# PWR.net
KiCad netlist of a schematic drawn in Altium Designer
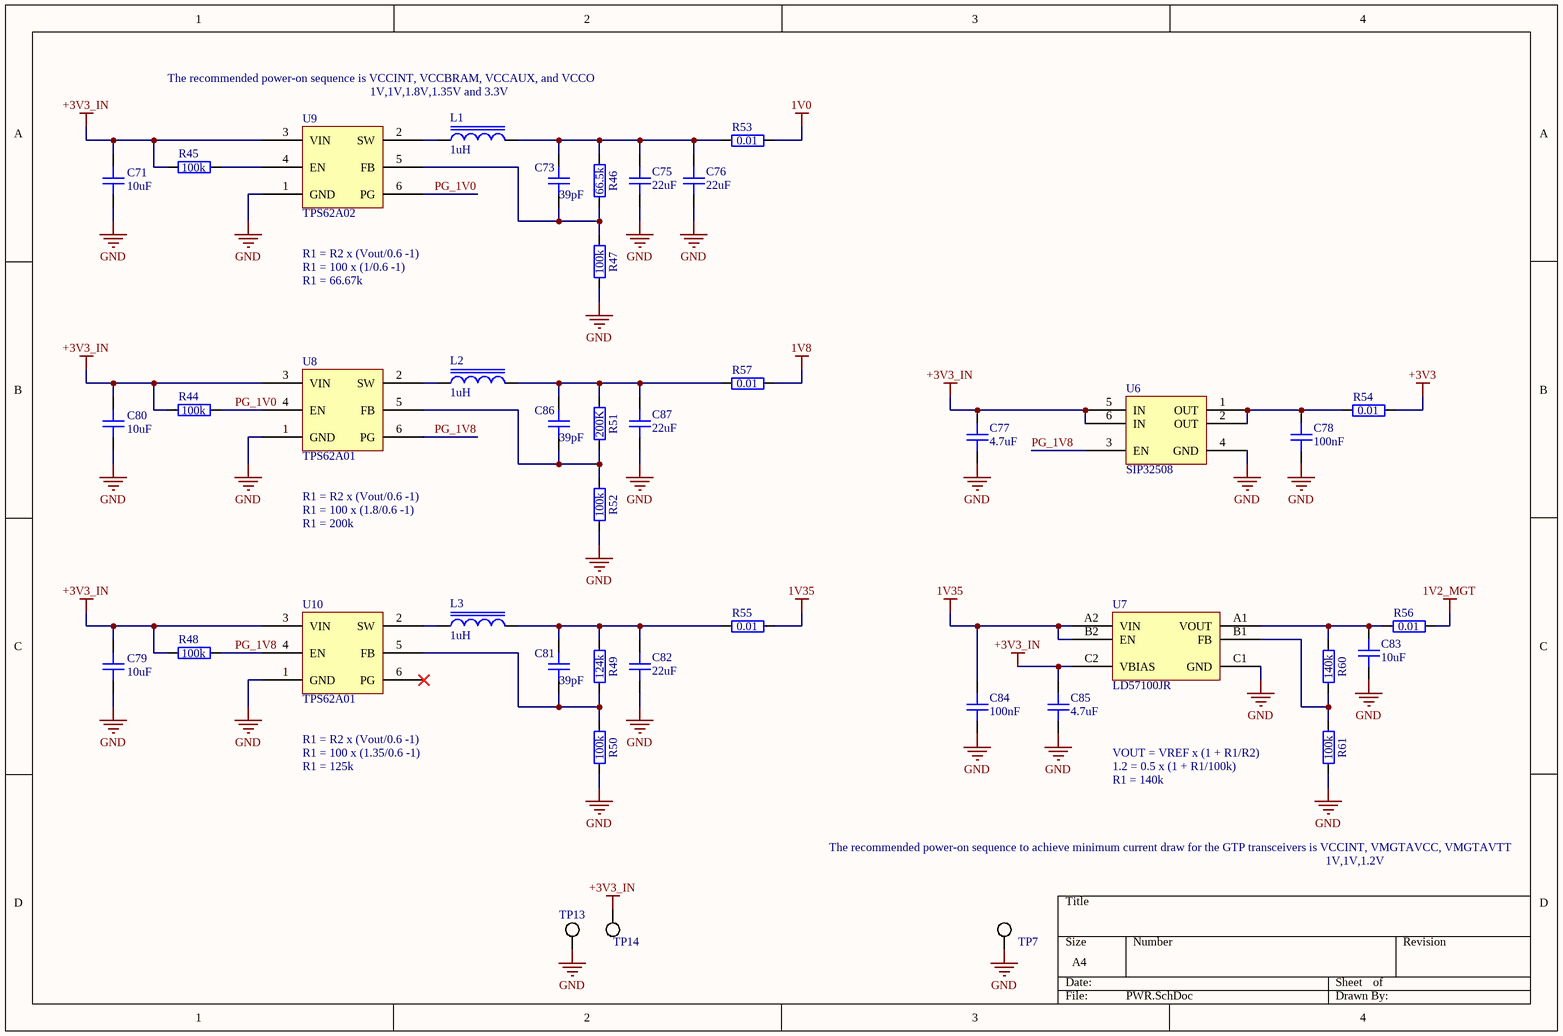
[diagram p0: PWR.SchDoc]

(export (version "E")
  (design (tool "Eeschema 10.0.6"))
  (components
    (comp (ref "C71")
      (value "10uF")
      (footprint "GEN_C_0603")
      (libsource (lib "DSO") (part "CAP 10uF 10V X5R 0603"))
    )
    (comp (ref "C73")
      (value "39pF")
      (footprint "GEN_C_0402")
      (libsource (lib "DSO") (part "CAP 39pF 50V C0G 0402"))
    )
    (comp (ref "C75")
      (value "22uF")
      (footprint "GEN_C_0805")
      (libsource (lib "DSO") (part "CAP 22uF 25V X5R 0805"))
    )
    (comp (ref "C76")
      (value "22uF")
      (footprint "GEN_C_0805")
      (libsource (lib "DSO") (part "CAP 22uF 25V X5R 0805"))
    )
    (comp (ref "C77")
      (value "4.7uF")
      (footprint "GEN_C_0402")
      (libsource (lib "DSO") (part "CAP 4.7uF 6.3V X5R 0402"))
    )
    (comp (ref "C78")
      (value "100nF")
      (footprint "GEN_C_0402")
      (libsource (lib "DSO") (part "CAP 100nF 16V X7R 0402"))
    )
    (comp (ref "C79")
      (value "10uF")
      (footprint "GEN_C_0603")
      (libsource (lib "DSO") (part "CAP 10uF 10V X5R 0603"))
    )
    (comp (ref "C80")
      (value "10uF")
      (footprint "GEN_C_0603")
      (libsource (lib "DSO") (part "CAP 10uF 10V X5R 0603"))
    )
    (comp (ref "C81")
      (value "39pF")
      (footprint "GEN_C_0402")
      (libsource (lib "DSO") (part "CAP 39pF 50V C0G 0402"))
    )
    (comp (ref "C82")
      (value "22uF")
      (footprint "GEN_C_0805")
      (libsource (lib "DSO") (part "CAP 22uF 25V X5R 0805"))
    )
    (comp (ref "C83")
      (value "10uF")
      (footprint "GEN_C_0603")
      (libsource (lib "DSO") (part "CAP 10uF 10V X5R 0603"))
    )
    (comp (ref "C84")
      (value "100nF")
      (footprint "GEN_C_0402")
      (libsource (lib "DSO") (part "CAP 100nF 16V X7R 0402"))
    )
    (comp (ref "C85")
      (value "4.7uF")
      (footprint "GEN_C_0402")
      (libsource (lib "DSO") (part "CAP 4.7uF 6.3V X5R 0402"))
    )
    (comp (ref "C86")
      (value "39pF")
      (footprint "GEN_C_0402")
      (libsource (lib "DSO") (part "CAP 39pF 50V C0G 0402"))
    )
    (comp (ref "C87")
      (value "22uF")
      (footprint "GEN_C_0805")
      (libsource (lib "DSO") (part "CAP 22uF 25V X5R 0805"))
    )
    (comp (ref "L1")
      (value "1uH")
      (footprint "GEN_L_1210")
      (libsource (lib "DSO") (part "IND 1uH 5.5A 32 MOHM 1210"))
    )
    (comp (ref "L2")
      (value "1uH")
      (footprint "GEN_L_1210")
      (libsource (lib "DSO") (part "IND 1uH 5.5A 32 MOHM 1210"))
    )
    (comp (ref "L3")
      (value "1uH")
      (footprint "GEN_L_1210")
      (libsource (lib "DSO") (part "IND 1uH 5.5A 32 MOHM 1210"))
    )
    (comp (ref "R44")
      (value "100k")
      (footprint "GEN_R_0402")
      (fields (field (name "TOLERANCE") "1%"))
      (libsource (lib "") (part "RES 100K OHM 1% 1/10W 0402_1"))
    )
    (comp (ref "R45")
      (value "100k")
      (footprint "GEN_R_0402")
      (fields (field (name "TOLERANCE") "1%"))
      (libsource (lib "") (part "RES 100K OHM 1% 1/10W 0402_1"))
    )
    (comp (ref "R46")
      (value "66.5k")
      (footprint "GEN_R_0402")
      (fields (field (name "TOLERANCE") "1%"))
      (libsource (lib "DSO") (part "RES 66.5K OHM 1% 1/16W 0402"))
    )
    (comp (ref "R47")
      (value "100k")
      (footprint "GEN_R_0402")
      (fields (field (name "TOLERANCE") "1%"))
      (libsource (lib "DSO") (part "RES 100K OHM 1% 1/10W 0402"))
    )
    (comp (ref "R48")
      (value "100k")
      (footprint "GEN_R_0402")
      (fields (field (name "TOLERANCE") "1%"))
      (libsource (lib "") (part "RES 100K OHM 1% 1/10W 0402_1"))
    )
    (comp (ref "R49")
      (value "124k")
      (footprint "GEN_R_0402")
      (fields (field (name "TOLERANCE") "1%"))
      (libsource (lib "DSO") (part "RES 124K OHM 1% 1/10W 0402"))
    )
    (comp (ref "R50")
      (value "100k")
      (footprint "GEN_R_0402")
      (fields (field (name "TOLERANCE") "1%"))
      (libsource (lib "DSO") (part "RES 100K OHM 1% 1/10W 0402"))
    )
    (comp (ref "R51")
      (value "200K")
      (footprint "GEN_R_0402")
      (fields (field (name "TOLERANCE") "1%"))
      (libsource (lib "DSO") (part "RES 200K OHM 1% 1/16W 0402"))
    )
    (comp (ref "R52")
      (value "100k")
      (footprint "GEN_R_0402")
      (fields (field (name "TOLERANCE") "1%"))
      (libsource (lib "DSO") (part "RES 100K OHM 1% 1/10W 0402"))
    )
    (comp (ref "R53")
      (value "0.01")
      (footprint "GEN_R_0603")
      (fields (field (name "TOLERANCE") "1%"))
      (libsource (lib "DSO") (part "RES 0.01 OHM 1% 1/4W 0603"))
    )
    (comp (ref "R54")
      (value "0.01")
      (footprint "GEN_R_0603")
      (fields (field (name "TOLERANCE") "1%"))
      (libsource (lib "DSO") (part "RES 0.01 OHM 1% 1/4W 0603"))
    )
    (comp (ref "R55")
      (value "0.01")
      (footprint "GEN_R_0603")
      (fields (field (name "TOLERANCE") "1%"))
      (libsource (lib "DSO") (part "RES 0.01 OHM 1% 1/4W 0603"))
    )
    (comp (ref "R56")
      (value "0.01")
      (footprint "GEN_R_0603")
      (fields (field (name "TOLERANCE") "1%"))
      (libsource (lib "DSO") (part "RES 0.01 OHM 1% 1/4W 0603"))
    )
    (comp (ref "R57")
      (value "0.01")
      (footprint "GEN_R_0603")
      (fields (field (name "TOLERANCE") "1%"))
      (libsource (lib "DSO") (part "RES 0.01 OHM 1% 1/4W 0603"))
    )
    (comp (ref "R60")
      (value "140k")
      (footprint "GEN_R_0402")
      (fields (field (name "TOLERANCE") "1%"))
      (libsource (lib "DSO") (part "RES 140K OHM 1% 1/10W 0402"))
    )
    (comp (ref "R61")
      (value "100k")
      (footprint "GEN_R_0402")
      (fields (field (name "TOLERANCE") "1%"))
      (libsource (lib "DSO") (part "RES 100K OHM 1% 1/10W 0402"))
    )
    (comp (ref "TP7") (value "PCB") (footprint "GEN_TP_PCB") (libsource (lib "DSO") (part "TP PCB 1mm")))
    (comp (ref "TP13") (value "PCB") (footprint "GEN_TP_PCB") (libsource (lib "DSO") (part "TP PCB 1mm")))
    (comp (ref "TP14") (value "PCB") (footprint "GEN_TP_PCB") (libsource (lib "DSO") (part "TP PCB 1mm")))
    (comp (ref "U6")
      (value "SIP32508")
      (footprint "VISH_TSOT6")
      (libsource (lib "DSO") (part "IC SWITCH LOAD SIP32508"))
    )
    (comp (ref "U7")
      (value "LD57100JR")
      (footprint "ST_FlipChip6")
      (libsource (lib "DSO") (part "IC LDO LD57100JR"))
    )
    (comp (ref "U8")
      (value "TPS62A01")
      (footprint "TI_SOT563_DRL0006A")
      (libsource (lib "DSO") (part "IC BUCK TPS62A01"))
    )
    (comp (ref "U9")
      (value "TPS62A02")
      (footprint "TI_SOT563_DRL0006A")
      (libsource (lib "DSO") (part "IC BUCK TPS62A02"))
    )
    (comp (ref "U10")
      (value "TPS62A01")
      (footprint "TI_SOT563_DRL0006A")
      (libsource (lib "DSO") (part "IC BUCK TPS62A01"))
    )
  )
  (nets
    (net (code "1") (name "+3V3") (class "Default")
      (node (ref "R54") (pin "2") (pinfunction "2_2") (pintype "passive"))
    )
    (net (code "2") (name "+3V3_IN") (class "Default")
      (node (ref "C71") (pin "2") (pinfunction "2_2") (pintype "passive"))
      (node (ref "C77") (pin "2") (pinfunction "2_2") (pintype "passive"))
      (node (ref "C79") (pin "2") (pinfunction "2_2") (pintype "passive"))
      (node (ref "C80") (pin "2") (pinfunction "2_2") (pintype "passive"))
      (node (ref "C85") (pin "2") (pinfunction "2_2") (pintype "passive"))
      (node (ref "R44") (pin "2") (pinfunction "2_2") (pintype "passive"))
      (node (ref "R45") (pin "2") (pinfunction "2_2") (pintype "passive"))
      (node (ref "R48") (pin "2") (pinfunction "2_2") (pintype "passive"))
      (node (ref "TP14") (pin "1") (pinfunction "1_1") (pintype "passive"))
      (node (ref "U10") (pin "3") (pinfunction "VIN_3") (pintype "power_in"))
      (node (ref "U6") (pin "5") (pinfunction "IN_5") (pintype "passive"))
      (node (ref "U6") (pin "6") (pinfunction "IN_6") (pintype "passive"))
      (node (ref "U7") (pin "C2") (pinfunction "VBIAS_C2") (pintype "passive"))
      (node (ref "U8") (pin "3") (pinfunction "VIN_3") (pintype "power_in"))
      (node (ref "U9") (pin "3") (pinfunction "VIN_3") (pintype "power_in"))
    )
    (net (code "3") (name "/PG_1V0") (class "Default")
      (node (ref "R44") (pin "1") (pinfunction "1_1") (pintype "passive"))
      (node (ref "U8") (pin "4") (pinfunction "EN_4") (pintype "passive"))
      (node (ref "U9") (pin "6") (pinfunction "PG_6") (pintype "passive"))
    )
    (net (code "4") (name "/PG_1V8") (class "Default")
      (node (ref "R48") (pin "1") (pinfunction "1_1") (pintype "passive"))
      (node (ref "U10") (pin "4") (pinfunction "EN_4") (pintype "passive"))
      (node (ref "U6") (pin "3") (pinfunction "EN_3") (pintype "passive"))
      (node (ref "U8") (pin "6") (pinfunction "PG_6") (pintype "passive"))
    )
    (net (code "5") (name "1V0") (class "Default")
      (node (ref "R53") (pin "2") (pinfunction "2_2") (pintype "passive"))
    )
    (net (code "6") (name "1V2_MGT") (class "Default")
      (node (ref "R56") (pin "2") (pinfunction "2_2") (pintype "passive"))
    )
    (net (code "7") (name "1V8") (class "Default")
      (node (ref "R57") (pin "2") (pinfunction "2_2") (pintype "passive"))
    )
    (net (code "8") (name "1V35") (class "Default")
      (node (ref "C84") (pin "2") (pinfunction "2_2") (pintype "passive"))
      (node (ref "R55") (pin "2") (pinfunction "2_2") (pintype "passive"))
      (node (ref "U7") (pin "A2") (pinfunction "VIN_A2") (pintype "passive"))
      (node (ref "U7") (pin "B2") (pinfunction "EN_B2") (pintype "passive"))
    )
    (net (code "9") (name "GND") (class "Default")
      (node (ref "C71") (pin "1") (pinfunction "1_1") (pintype "passive"))
      (node (ref "C75") (pin "1") (pinfunction "1_1") (pintype "passive"))
      (node (ref "C76") (pin "1") (pinfunction "1_1") (pintype "passive"))
      (node (ref "C77") (pin "1") (pinfunction "1_1") (pintype "passive"))
      (node (ref "C78") (pin "1") (pinfunction "1_1") (pintype "passive"))
      (node (ref "C79") (pin "1") (pinfunction "1_1") (pintype "passive"))
      (node (ref "C80") (pin "1") (pinfunction "1_1") (pintype "passive"))
      (node (ref "C82") (pin "1") (pinfunction "1_1") (pintype "passive"))
      (node (ref "C83") (pin "1") (pinfunction "1_1") (pintype "passive"))
      (node (ref "C84") (pin "1") (pinfunction "1_1") (pintype "passive"))
      (node (ref "C85") (pin "1") (pinfunction "1_1") (pintype "passive"))
      (node (ref "C87") (pin "1") (pinfunction "1_1") (pintype "passive"))
      (node (ref "R47") (pin "1") (pinfunction "1_1") (pintype "passive"))
      (node (ref "R50") (pin "1") (pinfunction "1_1") (pintype "passive"))
      (node (ref "R52") (pin "1") (pinfunction "1_1") (pintype "passive"))
      (node (ref "R61") (pin "1") (pinfunction "1_1") (pintype "passive"))
      (node (ref "TP13") (pin "1") (pinfunction "1_1") (pintype "passive"))
      (node (ref "TP7") (pin "1") (pinfunction "1_1") (pintype "passive"))
      (node (ref "U10") (pin "1") (pinfunction "GND_1") (pintype "power_in"))
      (node (ref "U6") (pin "4") (pinfunction "GND_4") (pintype "passive"))
      (node (ref "U7") (pin "C1") (pinfunction "GND_C1") (pintype "passive"))
      (node (ref "U8") (pin "1") (pinfunction "GND_1") (pintype "power_in"))
      (node (ref "U9") (pin "1") (pinfunction "GND_1") (pintype "power_in"))
    )
    (net (code "10") (name "Net-(C73-Pad2)") (class "Default")
      (node (ref "C73") (pin "2") (pinfunction "2_2") (pintype "passive"))
      (node (ref "C75") (pin "2") (pinfunction "2_2") (pintype "passive"))
      (node (ref "C76") (pin "2") (pinfunction "2_2") (pintype "passive"))
      (node (ref "L1") (pin "2") (pinfunction "2_2") (pintype "passive"))
      (node (ref "R46") (pin "2") (pinfunction "2_2") (pintype "passive"))
      (node (ref "R53") (pin "1") (pinfunction "1_1") (pintype "passive"))
    )
    (net (code "11") (name "Net-(C78-Pad2)") (class "Default")
      (node (ref "C78") (pin "2") (pinfunction "2_2") (pintype "passive"))
      (node (ref "R54") (pin "1") (pinfunction "1_1") (pintype "passive"))
      (node (ref "U6") (pin "1") (pinfunction "OUT_1") (pintype "passive"))
      (node (ref "U6") (pin "2") (pinfunction "OUT_2") (pintype "passive"))
    )
    (net (code "12") (name "Net-(C81-Pad2)") (class "Default")
      (node (ref "C81") (pin "2") (pinfunction "2_2") (pintype "passive"))
      (node (ref "C82") (pin "2") (pinfunction "2_2") (pintype "passive"))
      (node (ref "L3") (pin "2") (pinfunction "2_2") (pintype "passive"))
      (node (ref "R49") (pin "2") (pinfunction "2_2") (pintype "passive"))
      (node (ref "R55") (pin "1") (pinfunction "1_1") (pintype "passive"))
    )
    (net (code "13") (name "Net-(C86-Pad2)") (class "Default")
      (node (ref "C86") (pin "2") (pinfunction "2_2") (pintype "passive"))
      (node (ref "C87") (pin "2") (pinfunction "2_2") (pintype "passive"))
      (node (ref "L2") (pin "2") (pinfunction "2_2") (pintype "passive"))
      (node (ref "R51") (pin "2") (pinfunction "2_2") (pintype "passive"))
      (node (ref "R57") (pin "1") (pinfunction "1_1") (pintype "passive"))
    )
    (net (code "14") (name "Net-(U7-FB)") (class "Default")
      (node (ref "R60") (pin "1") (pinfunction "1_1") (pintype "passive"))
      (node (ref "R61") (pin "2") (pinfunction "2_2") (pintype "passive"))
      (node (ref "U7") (pin "B1") (pinfunction "FB_B1") (pintype "passive"))
    )
    (net (code "15") (name "Net-(U7-VOUT)") (class "Default")
      (node (ref "C83") (pin "2") (pinfunction "2_2") (pintype "passive"))
      (node (ref "R56") (pin "1") (pinfunction "1_1") (pintype "passive"))
      (node (ref "R60") (pin "2") (pinfunction "2_2") (pintype "passive"))
      (node (ref "U7") (pin "A1") (pinfunction "VOUT_A1") (pintype "passive"))
    )
    (net (code "16") (name "Net-(U8-FB)") (class "Default")
      (node (ref "C86") (pin "1") (pinfunction "1_1") (pintype "passive"))
      (node (ref "R51") (pin "1") (pinfunction "1_1") (pintype "passive"))
      (node (ref "R52") (pin "2") (pinfunction "2_2") (pintype "passive"))
      (node (ref "U8") (pin "5") (pinfunction "FB_5") (pintype "passive"))
    )
    (net (code "17") (name "Net-(U8-SW)") (class "Default")
      (node (ref "L2") (pin "1") (pinfunction "1_1") (pintype "passive"))
      (node (ref "U8") (pin "2") (pinfunction "SW_2") (pintype "passive"))
    )
    (net (code "18") (name "Net-(U9-EN)") (class "Default")
      (node (ref "R45") (pin "1") (pinfunction "1_1") (pintype "passive"))
      (node (ref "U9") (pin "4") (pinfunction "EN_4") (pintype "passive"))
    )
    (net (code "19") (name "Net-(U9-FB)") (class "Default")
      (node (ref "C73") (pin "1") (pinfunction "1_1") (pintype "passive"))
      (node (ref "R46") (pin "1") (pinfunction "1_1") (pintype "passive"))
      (node (ref "R47") (pin "2") (pinfunction "2_2") (pintype "passive"))
      (node (ref "U9") (pin "5") (pinfunction "FB_5") (pintype "passive"))
    )
    (net (code "20") (name "Net-(U9-SW)") (class "Default")
      (node (ref "L1") (pin "1") (pinfunction "1_1") (pintype "passive"))
      (node (ref "U9") (pin "2") (pinfunction "SW_2") (pintype "passive"))
    )
    (net (code "21") (name "Net-(U10-FB)") (class "Default")
      (node (ref "C81") (pin "1") (pinfunction "1_1") (pintype "passive"))
      (node (ref "R49") (pin "1") (pinfunction "1_1") (pintype "passive"))
      (node (ref "R50") (pin "2") (pinfunction "2_2") (pintype "passive"))
      (node (ref "U10") (pin "5") (pinfunction "FB_5") (pintype "passive"))
    )
    (net (code "22") (name "Net-(U10-SW)") (class "Default")
      (node (ref "L3") (pin "1") (pinfunction "1_1") (pintype "passive"))
      (node (ref "U10") (pin "2") (pinfunction "SW_2") (pintype "passive"))
    )
    (net (code "23") (name "unconnected-(U10-PG-Pad6)") (class "Default")
      (node (ref "U10") (pin "6") (pinfunction "PG_6") (pintype "passive+no_connect"))
    )
  )
)
